# breaking_bitcoin.net
KiCad netlist of a schematic drawn in EAGLE
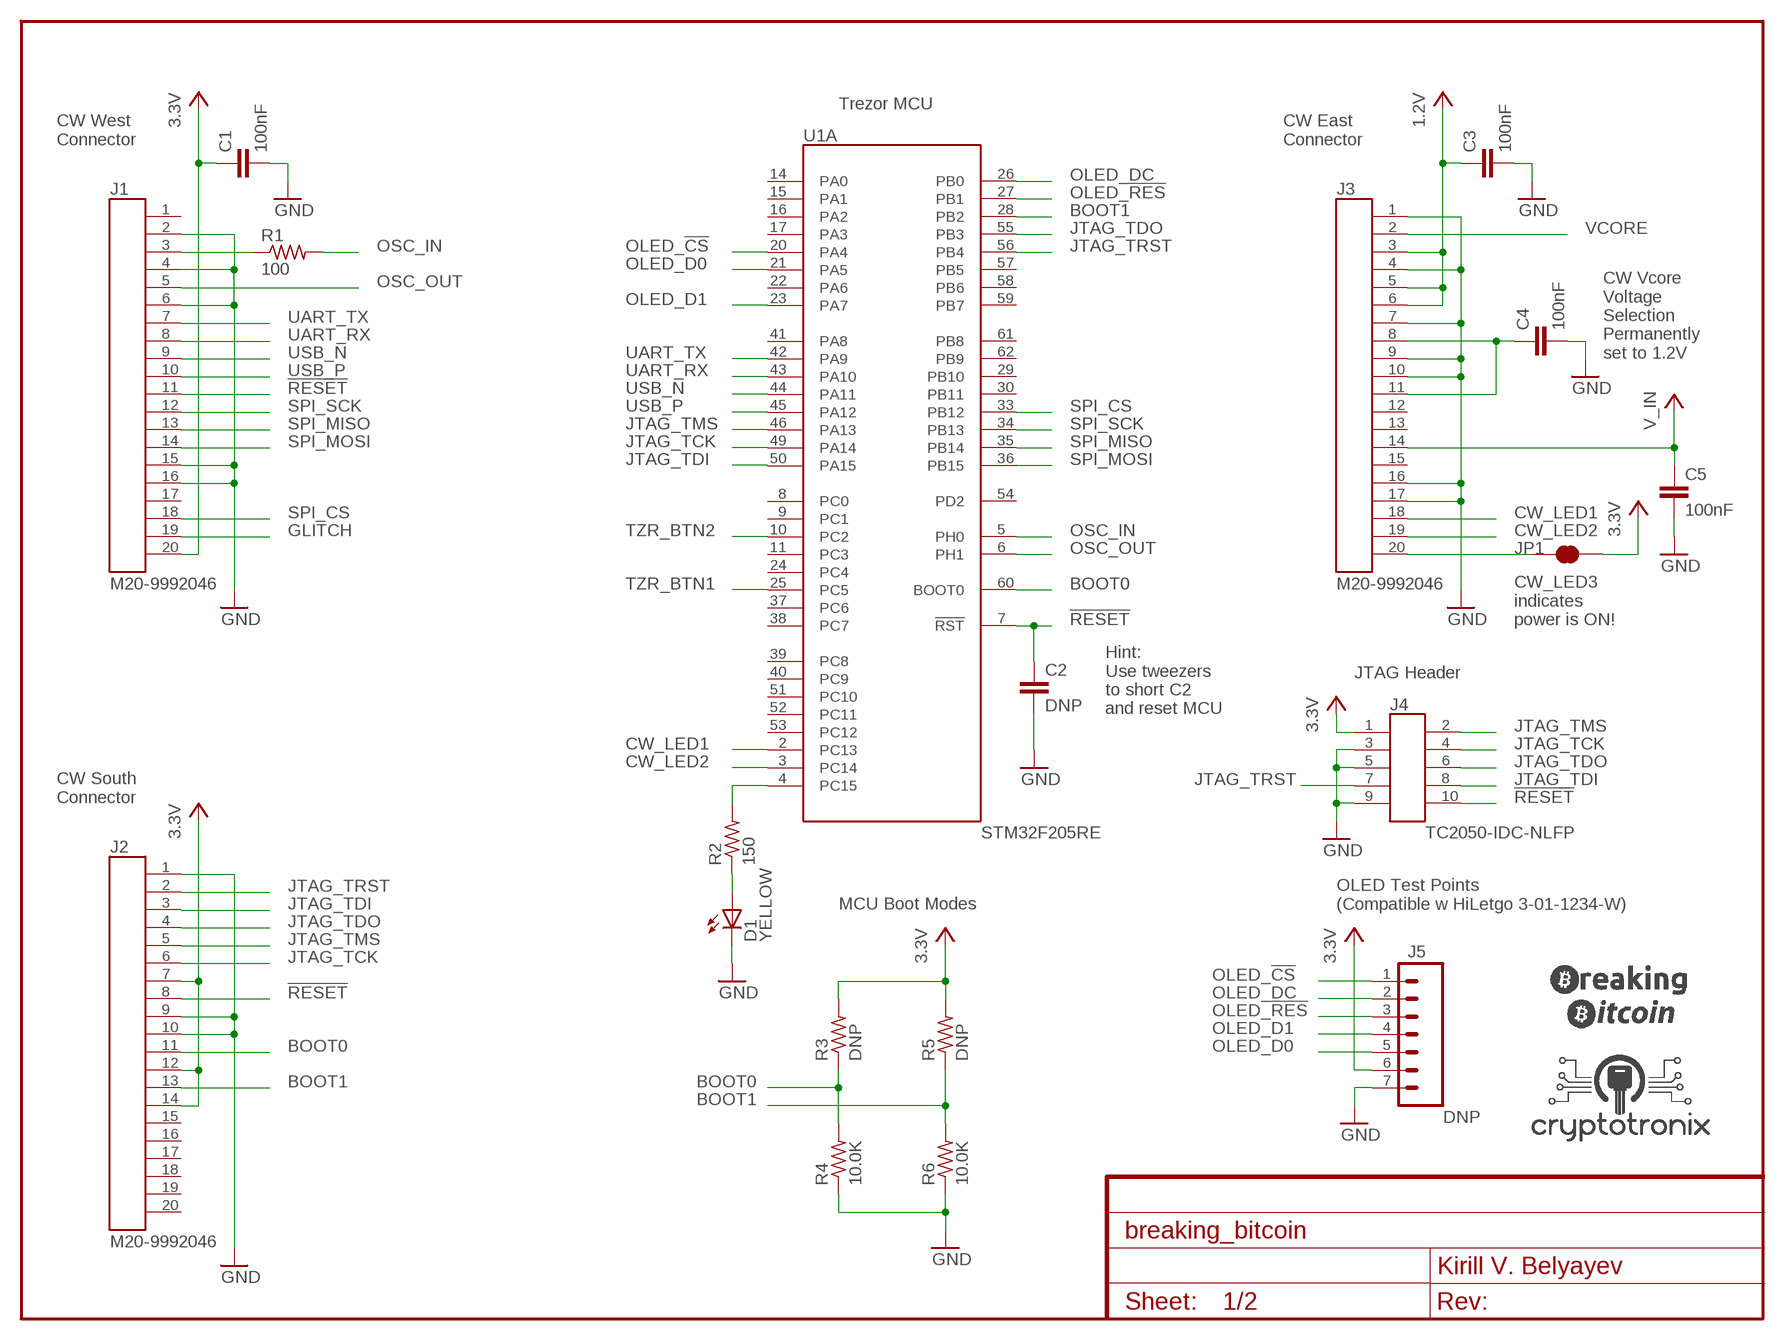
[diagram p0: schematic, sheet 1]
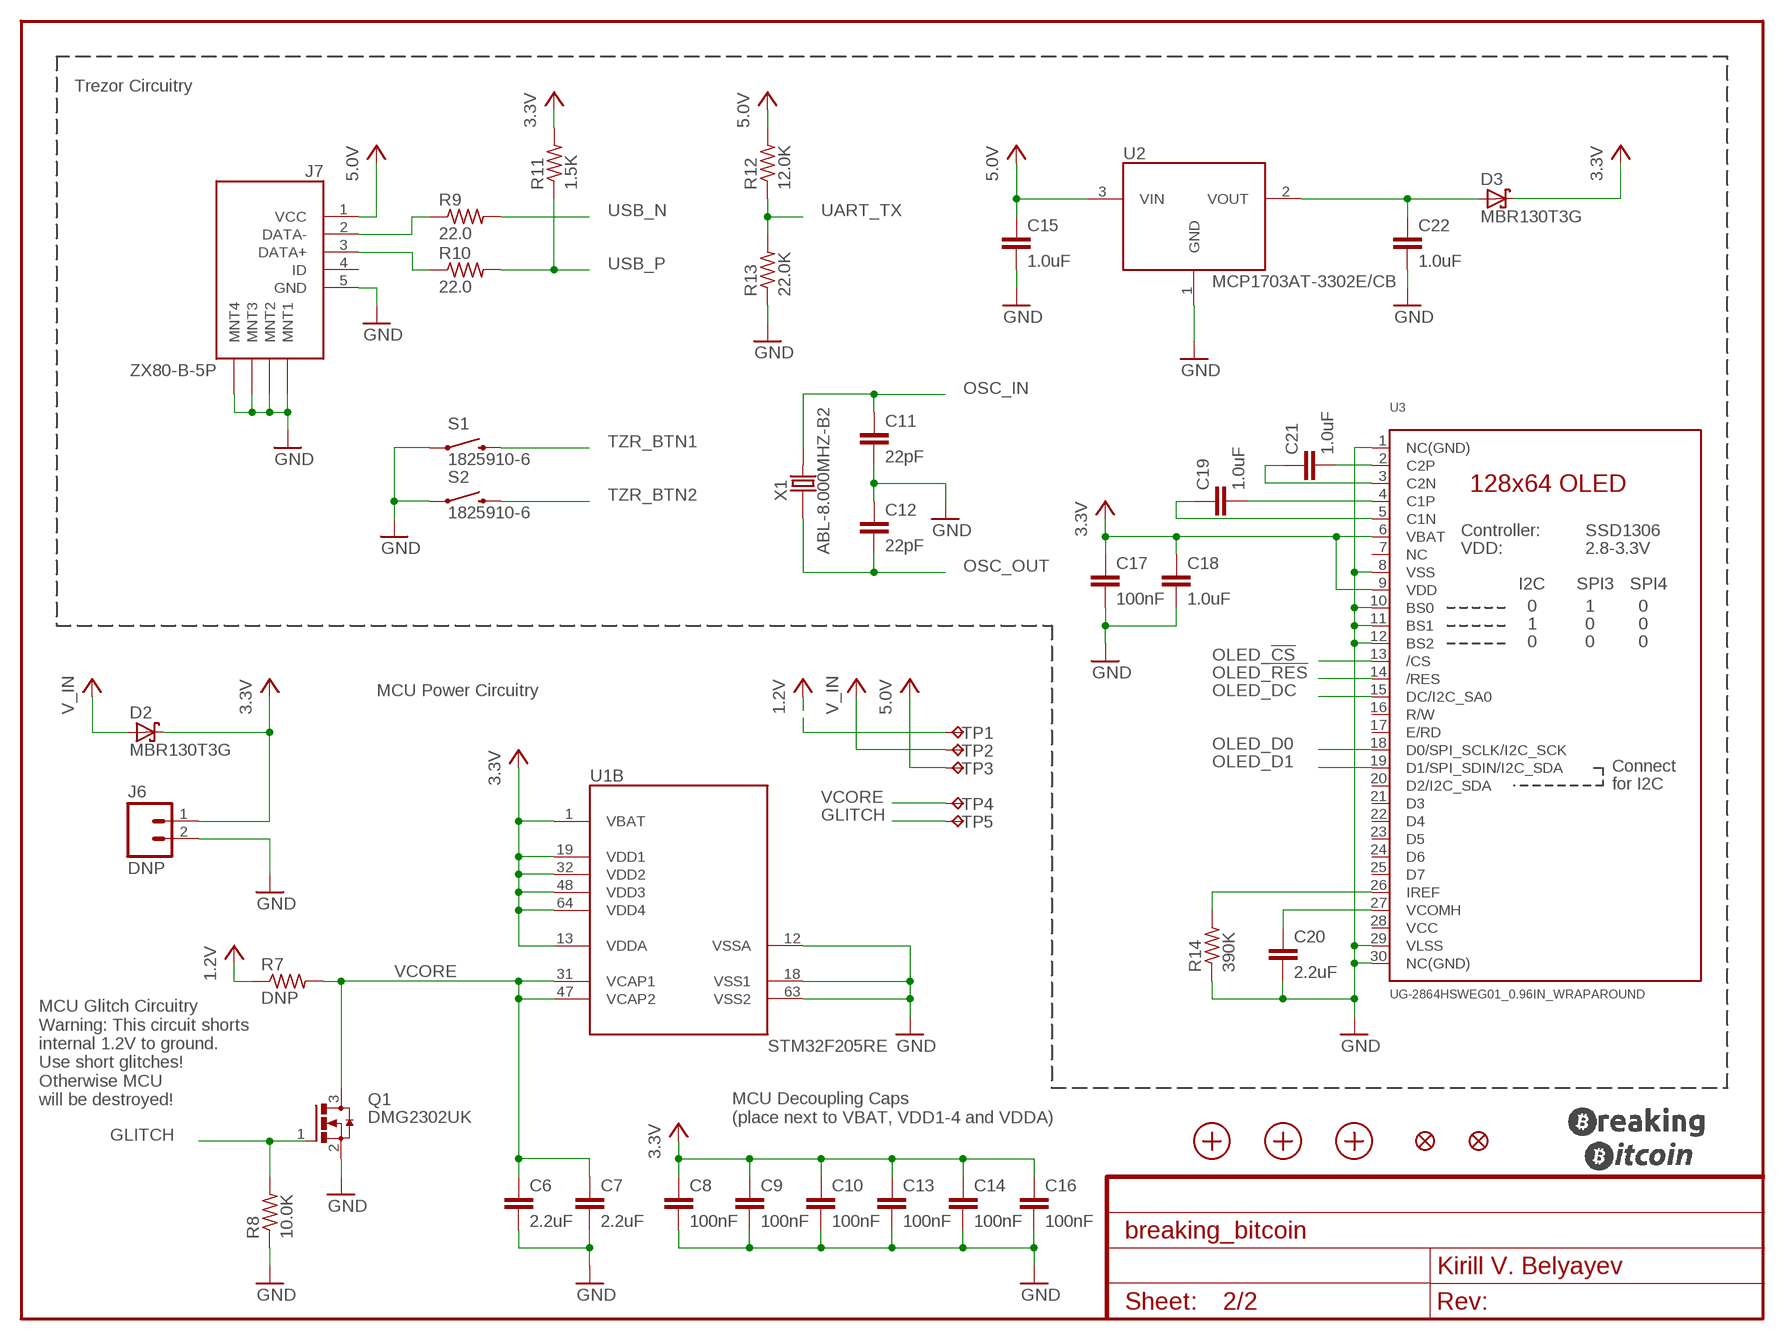
[diagram p1: schematic, sheet 2]

(export (version "E")
  (design (tool "Eeschema 10.0.6"))
  (components
    (comp (ref "C6")
      (value "2.2uF")
      (footprint "eagle-import:C0603")
      (libsource (lib "eagle-import") (part "C-EUC0603"))
    )
    (comp (ref "C7")
      (value "2.2uF")
      (footprint "eagle-import:C0603")
      (libsource (lib "eagle-import") (part "C-EUC0603"))
    )
    (comp (ref "C8")
      (value "100nF")
      (footprint "eagle-import:C0603")
      (libsource (lib "eagle-import") (part "C-EUC0603"))
    )
    (comp (ref "C9")
      (value "100nF")
      (footprint "eagle-import:C0603")
      (libsource (lib "eagle-import") (part "C-EUC0603"))
    )
    (comp (ref "C10")
      (value "100nF")
      (footprint "eagle-import:C0603")
      (libsource (lib "eagle-import") (part "C-EUC0603"))
    )
    (comp (ref "C11")
      (value "22pF")
      (footprint "eagle-import:C0603")
      (libsource (lib "eagle-import") (part "C-EUC0603"))
    )
    (comp (ref "C12")
      (value "22pF")
      (footprint "eagle-import:C0603")
      (libsource (lib "eagle-import") (part "C-EUC0603"))
    )
    (comp (ref "C13")
      (value "100nF")
      (footprint "eagle-import:C0603")
      (libsource (lib "eagle-import") (part "C-EUC0603"))
    )
    (comp (ref "C14")
      (value "100nF")
      (footprint "eagle-import:C0603")
      (libsource (lib "eagle-import") (part "C-EUC0603"))
    )
    (comp (ref "C15")
      (value "1.0uF")
      (footprint "eagle-import:C0603")
      (libsource (lib "eagle-import") (part "C-EUC0603"))
    )
    (comp (ref "C16")
      (value "100nF")
      (footprint "eagle-import:C0603")
      (libsource (lib "eagle-import") (part "C-EUC0603"))
    )
    (comp (ref "C17")
      (value "100nF")
      (footprint "eagle-import:C0603")
      (libsource (lib "eagle-import") (part "C-EUC0603"))
    )
    (comp (ref "C18")
      (value "1.0uF")
      (footprint "eagle-import:C0603")
      (libsource (lib "eagle-import") (part "C-EUC0603"))
    )
    (comp (ref "C19")
      (value "1.0uF")
      (footprint "eagle-import:C0603")
      (libsource (lib "eagle-import") (part "C-EUC0603"))
    )
    (comp (ref "C20")
      (value "2.2uF")
      (footprint "eagle-import:C0603")
      (libsource (lib "eagle-import") (part "C-EUC0603"))
    )
    (comp (ref "C21")
      (value "1.0uF")
      (footprint "eagle-import:C0603")
      (libsource (lib "eagle-import") (part "C-EUC0603"))
    )
    (comp (ref "C22")
      (value "1.0uF")
      (footprint "eagle-import:C0603")
      (libsource (lib "eagle-import") (part "C-EUC0603"))
    )
    (comp (ref "D2")
      (value "MBR130T3G")
      (footprint "eagle-import:SOD123")
      (fields (field (name "MANUFACTURER") "ON Semiconductor"))
      (libsource (lib "eagle-import") (part "MBR130T3G"))
    )
    (comp (ref "D3")
      (value "MBR130T3G")
      (footprint "eagle-import:SOD123")
      (fields (field (name "MANUFACTURER") "ON Semiconductor"))
      (libsource (lib "eagle-import") (part "MBR130T3G"))
    )
    (comp (ref "FD1")
      (value "FIDUCIALUFIDUCIAL")
      (footprint "eagle-import:MICRO-FIDUCIAL")
      (libsource (lib "eagle-import") (part "FIDUCIALUFIDUCIAL"))
    )
    (comp (ref "FD2")
      (value "FIDUCIALUFIDUCIAL")
      (footprint "eagle-import:MICRO-FIDUCIAL")
      (libsource (lib "eagle-import") (part "FIDUCIALUFIDUCIAL"))
    )
    (comp (ref "J6")
      (value "DNP")
      (footprint "eagle-import:M20-9990246")
      (fields (field (name "MAN-PART_NUM") "M20-9990246") (field (name "MANUFACTURER") "Harwin Inc."))
      (libsource (lib "eagle-import") (part "M20-9990246"))
    )
    (comp (ref "J7")
      (value "ZX80-B-5P")
      (footprint "eagle-import:ZX80-B-5P")
      (fields (field (name "MAN-PART_NUM") "ZX80-B-5P(30)") (field (name "MANUFACTURER") "Hirose"))
      (libsource (lib "eagle-import") (part "ZX80-B-5P"))
    )
    (comp (ref "MNT1")
      (value "MOUNT-HOLE-NO-PLATE4-40")
      (footprint "eagle-import:MOUNT-HOLE-NO-PLATE-4-40")
      (libsource (lib "eagle-import") (part "MOUNT-HOLE-NO-PLATE4-40"))
    )
    (comp (ref "MNT2")
      (value "MOUNT-HOLE-NO-PLATE4-40")
      (footprint "eagle-import:MOUNT-HOLE-NO-PLATE-4-40")
      (libsource (lib "eagle-import") (part "MOUNT-HOLE-NO-PLATE4-40"))
    )
    (comp (ref "MNT3")
      (value "MOUNT-HOLE-NO-PLATE4-40")
      (footprint "eagle-import:MOUNT-HOLE-NO-PLATE-4-40")
      (libsource (lib "eagle-import") (part "MOUNT-HOLE-NO-PLATE4-40"))
    )
    (comp (ref "Q1")
      (value "DMG2302UK")
      (footprint "eagle-import:DMG2302UK")
      (fields (field (name "MANUFACTURER") "Diodes Inc."))
      (libsource (lib "eagle-import") (part "DMG2302UK"))
    )
    (comp (ref "R7")
      (value "DNP")
      (footprint "eagle-import:R0603")
      (libsource (lib "eagle-import") (part "R-US_R0603"))
    )
    (comp (ref "R8")
      (value "10.0K")
      (footprint "eagle-import:R0603")
      (libsource (lib "eagle-import") (part "R-US_R0603"))
    )
    (comp (ref "R9")
      (value "22.0")
      (footprint "eagle-import:R0603")
      (libsource (lib "eagle-import") (part "R-US_R0603"))
    )
    (comp (ref "R10")
      (value "22.0")
      (footprint "eagle-import:R0603")
      (libsource (lib "eagle-import") (part "R-US_R0603"))
    )
    (comp (ref "R11")
      (value "1.5K")
      (footprint "eagle-import:R0603")
      (libsource (lib "eagle-import") (part "R-US_R0603"))
    )
    (comp (ref "R12")
      (value "12.0K")
      (footprint "eagle-import:R0603")
      (libsource (lib "eagle-import") (part "R-US_R0603"))
    )
    (comp (ref "R13")
      (value "22.0K")
      (footprint "eagle-import:R0603")
      (libsource (lib "eagle-import") (part "R-US_R0603"))
    )
    (comp (ref "R14")
      (value "390K")
      (footprint "eagle-import:R0603")
      (libsource (lib "eagle-import") (part "R-US_R0603"))
    )
    (comp (ref "S1")
      (value "1825910-6")
      (footprint "eagle-import:SWITCH-TACT-TH")
      (fields
        (field (name "MANUFACTURER") "TE Connectivity")
        (field (name "MAN-PART_NUM") "1825910-6")
        (field (name "MANUFACTURER_1") "TE Connectivity")
      )
      (libsource (lib "eagle-import") (part "SWITCH-TACT-TH"))
    )
    (comp (ref "S2")
      (value "1825910-6")
      (footprint "eagle-import:SWITCH-TACT-TH")
      (fields
        (field (name "MANUFACTURER") "TE Connectivity")
        (field (name "MAN-PART_NUM") "1825910-6")
        (field (name "MANUFACTURER_1") "TE Connectivity")
      )
      (libsource (lib "eagle-import") (part "SWITCH-TACT-TH"))
    )
    (comp (ref "TP1")
      (value "TEST-POINT40MIL")
      (footprint "eagle-import:TEST-POINT-40MILL")
      (libsource (lib "eagle-import") (part "TEST-POINT40MIL"))
    )
    (comp (ref "TP2")
      (value "TEST-POINT40MIL")
      (footprint "eagle-import:TEST-POINT-40MILL")
      (libsource (lib "eagle-import") (part "TEST-POINT40MIL"))
    )
    (comp (ref "TP3")
      (value "TEST-POINT40MIL")
      (footprint "eagle-import:TEST-POINT-40MILL")
      (libsource (lib "eagle-import") (part "TEST-POINT40MIL"))
    )
    (comp (ref "TP4")
      (value "TEST-POINT40MIL")
      (footprint "eagle-import:TEST-POINT-40MILL")
      (libsource (lib "eagle-import") (part "TEST-POINT40MIL"))
    )
    (comp (ref "TP5")
      (value "TEST-POINT40MIL")
      (footprint "eagle-import:TEST-POINT-40MILL")
      (libsource (lib "eagle-import") (part "TEST-POINT40MIL"))
    )
    (comp (ref "U$3")
      (value "BB_LOGO")
      (footprint "eagle-import:BB_LOGO")
      (libsource (lib "eagle-import") (part "BB_LOGO"))
    )
    (comp (ref "U1")
      (value "STM32F205RE")
      (footprint "eagle-import:LQFP64")
      (fields (field (name "MANUFACTURER") "STMicroelectronics"))
      (libsource (lib "eagle-import") (part "STM32F205RE"))
    )
    (comp (ref "U2")
      (value "MCP1703AT-3302E/CB")
      (footprint "eagle-import:MCP1703AT-3302E_CB")
      (fields (field (name "MANUFACTURER") "Microchip Technology"))
      (libsource (lib "eagle-import") (part "MCP1703AT-3302E/CB"))
    )
    (comp (ref "U3")
      (value "UG-2864HSWEG01_0.96IN_WRAPAROUND")
      (footprint "eagle-import:UG-2864HSWEG01_0.96IN_WRAPAROUND")
      (libsource (lib "eagle-import") (part "DISP_OLED_UG-2864HSWEG010.96{dblquote}"))
    )
    (comp (ref "X1")
      (value "ABL-8.000MHZ-B2")
      (footprint "eagle-import:ABL-8.000MHZ-B2")
      (fields (field (name "MANUFACTURER") "Abracon"))
      (libsource (lib "eagle-import") (part "ABL-8.000MHZ-B2"))
    )
    (comp (ref "C1")
      (value "100nF")
      (footprint "eagle-import:C0603")
      (libsource (lib "eagle-import") (part "C-EUC0603"))
    )
    (comp (ref "C2")
      (value "DNP")
      (footprint "eagle-import:C0603")
      (libsource (lib "eagle-import") (part "C-EUC0603"))
    )
    (comp (ref "C3")
      (value "100nF")
      (footprint "eagle-import:C0603")
      (libsource (lib "eagle-import") (part "C-EUC0603"))
    )
    (comp (ref "C4")
      (value "100nF")
      (footprint "eagle-import:C0603")
      (libsource (lib "eagle-import") (part "C-EUC0603"))
    )
    (comp (ref "C5")
      (value "100nF")
      (footprint "eagle-import:C0603")
      (libsource (lib "eagle-import") (part "C-EUC0603"))
    )
    (comp (ref "D1")
      (value "YELLOW")
      (footprint "eagle-import:0603")
      (fields (field (name "MAN-PART_NUM") "LTST-C190") (field (name "MANUFACTURER") "Lite-On Inc."))
      (libsource (lib "eagle-import") (part "LTST-C190YKT"))
    )
    (comp (ref "J1")
      (value "M20-9992046")
      (footprint "eagle-import:M20-9992046")
      (fields (field (name "MANUFACTURER") "Harwin Inc."))
      (libsource (lib "eagle-import") (part "M20-9992046"))
    )
    (comp (ref "J2")
      (value "M20-9992046")
      (footprint "eagle-import:M20-9992046")
      (fields (field (name "MANUFACTURER") "Harwin Inc."))
      (libsource (lib "eagle-import") (part "M20-9992046"))
    )
    (comp (ref "J3")
      (value "M20-9992046")
      (footprint "eagle-import:M20-9992046")
      (fields (field (name "MANUFACTURER") "Harwin Inc."))
      (libsource (lib "eagle-import") (part "M20-9992046"))
    )
    (comp (ref "J4")
      (value "TC2050-IDC-NLFP")
      (footprint "eagle-import:TC2050-IDC-NLFP")
      (fields (field (name "MANUFACTURER") "Tag Connect"))
      (libsource (lib "eagle-import") (part "TC2050-IDC-NLFP"))
    )
    (comp (ref "J5")
      (value "DNP")
      (footprint "eagle-import:1X07")
      (libsource (lib "eagle-import") (part "M07"))
    )
    (comp (ref "JP1")
      (value "JUMPER-PAD-2-NC_BY_TRACE")
      (footprint "eagle-import:PAD-JUMPER-2-NC_BY_TRACE_YES_SILK")
      (libsource (lib "eagle-import") (part "JUMPER-PAD-2-NC_BY_TRACE"))
    )
    (comp (ref "R1")
      (value "100")
      (footprint "eagle-import:R0603")
      (libsource (lib "eagle-import") (part "R-US_R0603"))
    )
    (comp (ref "R2")
      (value "150")
      (footprint "eagle-import:R0603")
      (libsource (lib "eagle-import") (part "R-US_R0603"))
    )
    (comp (ref "R3")
      (value "DNP")
      (footprint "eagle-import:R0603")
      (libsource (lib "eagle-import") (part "R-US_R0603"))
    )
    (comp (ref "R4")
      (value "10.0K")
      (footprint "eagle-import:R0603")
      (libsource (lib "eagle-import") (part "R-US_R0603"))
    )
    (comp (ref "R5")
      (value "DNP")
      (footprint "eagle-import:R0603")
      (libsource (lib "eagle-import") (part "R-US_R0603"))
    )
    (comp (ref "R6")
      (value "10.0K")
      (footprint "eagle-import:R0603")
      (libsource (lib "eagle-import") (part "R-US_R0603"))
    )
    (comp (ref "U$1")
      (value "BB_LOGO")
      (footprint "eagle-import:BB_LOGO")
      (libsource (lib "eagle-import") (part "BB_LOGO"))
    )
    (comp (ref "U$2")
      (value "CRYPTOTRONIX_LOGO")
      (footprint "eagle-import:CRYPTOTRONIX_LOGO")
      (libsource (lib "eagle-import") (part "CRYPTOTRONIX_LOGO"))
    )
  )
  (nets
    (net (code "1") (name "0V") (class "Default")
      (node (ref "C1") (pin "2") (pinfunction "2_2") (pintype "passive"))
      (node (ref "C10") (pin "2") (pinfunction "2_2") (pintype "passive"))
      (node (ref "C11") (pin "2") (pinfunction "2_2") (pintype "passive"))
      (node (ref "C12") (pin "1") (pinfunction "1_1") (pintype "passive"))
      (node (ref "C13") (pin "2") (pinfunction "2_2") (pintype "passive"))
      (node (ref "C14") (pin "2") (pinfunction "2_2") (pintype "passive"))
      (node (ref "C15") (pin "2") (pinfunction "2_2") (pintype "passive"))
      (node (ref "C16") (pin "2") (pinfunction "2_2") (pintype "passive"))
      (node (ref "C17") (pin "2") (pinfunction "2_2") (pintype "passive"))
      (node (ref "C18") (pin "2") (pinfunction "2_2") (pintype "passive"))
      (node (ref "C2") (pin "2") (pinfunction "2_2") (pintype "passive"))
      (node (ref "C20") (pin "2") (pinfunction "2_2") (pintype "passive"))
      (node (ref "C22") (pin "2") (pinfunction "2_2") (pintype "passive"))
      (node (ref "C3") (pin "2") (pinfunction "2_2") (pintype "passive"))
      (node (ref "C4") (pin "2") (pinfunction "2_2") (pintype "passive"))
      (node (ref "C5") (pin "2") (pinfunction "2_2") (pintype "passive"))
      (node (ref "C6") (pin "2") (pinfunction "2_2") (pintype "passive"))
      (node (ref "C7") (pin "2") (pinfunction "2_2") (pintype "passive"))
      (node (ref "C8") (pin "2") (pinfunction "2_2") (pintype "passive"))
      (node (ref "C9") (pin "2") (pinfunction "2_2") (pintype "passive"))
      (node (ref "D1") (pin "C") (pinfunction "C_C") (pintype "passive"))
      (node (ref "J1") (pin "15") (pinfunction "P$15_15") (pintype "bidirectional"))
      (node (ref "J1") (pin "16") (pinfunction "P$16_16") (pintype "bidirectional"))
      (node (ref "J1") (pin "2") (pinfunction "P$2_2") (pintype "bidirectional"))
      (node (ref "J1") (pin "4") (pinfunction "P$4_4") (pintype "bidirectional"))
      (node (ref "J1") (pin "6") (pinfunction "P$6_6") (pintype "bidirectional"))
      (node (ref "J2") (pin "1") (pinfunction "P$1_1") (pintype "bidirectional"))
      (node (ref "J2") (pin "10") (pinfunction "P$10_10") (pintype "bidirectional"))
      (node (ref "J2") (pin "9") (pinfunction "P$9_9") (pintype "bidirectional"))
      (node (ref "J3") (pin "1") (pinfunction "P$1_1") (pintype "bidirectional"))
      (node (ref "J3") (pin "10") (pinfunction "P$10_10") (pintype "bidirectional"))
      (node (ref "J3") (pin "16") (pinfunction "P$16_16") (pintype "bidirectional"))
      (node (ref "J3") (pin "17") (pinfunction "P$17_17") (pintype "bidirectional"))
      (node (ref "J3") (pin "4") (pinfunction "P$4_4") (pintype "bidirectional"))
      (node (ref "J3") (pin "7") (pinfunction "P$7_7") (pintype "bidirectional"))
      (node (ref "J3") (pin "9") (pinfunction "P$9_9") (pintype "bidirectional"))
      (node (ref "J4") (pin "3") (pinfunction "P$3_3") (pintype "bidirectional"))
      (node (ref "J4") (pin "5") (pinfunction "P$5_5") (pintype "bidirectional"))
      (node (ref "J4") (pin "9") (pinfunction "P$9_9") (pintype "bidirectional"))
      (node (ref "J5") (pin "7") (pinfunction "7_7") (pintype "passive"))
      (node (ref "J6") (pin "2") (pinfunction "2_2") (pintype "passive"))
      (node (ref "J7") (pin "5") (pinfunction "GND_5") (pintype "bidirectional"))
      (node (ref "J7") (pin "M1") (pinfunction "MNT1_M1") (pintype "bidirectional"))
      (node (ref "J7") (pin "M2") (pinfunction "MNT2_M2") (pintype "bidirectional"))
      (node (ref "J7") (pin "M3") (pinfunction "MNT3_M3") (pintype "bidirectional"))
      (node (ref "J7") (pin "M4") (pinfunction "MNT4_M4") (pintype "bidirectional"))
      (node (ref "Q1") (pin "2") (pinfunction "S_2") (pintype "passive"))
      (node (ref "R13") (pin "1") (pinfunction "1_1") (pintype "passive"))
      (node (ref "R14") (pin "1") (pinfunction "1_1") (pintype "passive"))
      (node (ref "R4") (pin "1") (pinfunction "1_1") (pintype "passive"))
      (node (ref "R6") (pin "1") (pinfunction "1_1") (pintype "passive"))
      (node (ref "R8") (pin "1") (pinfunction "1_1") (pintype "passive"))
      (node (ref "S1") (pin "1") (pinfunction "1_1") (pintype "passive"))
      (node (ref "S2") (pin "1") (pinfunction "1_1") (pintype "passive"))
      (node (ref "U1") (pin "12") (pinfunction "VSSA_12") (pintype "bidirectional"))
      (node (ref "U1") (pin "18") (pinfunction "VSS1_18") (pintype "bidirectional"))
      (node (ref "U1") (pin "63") (pinfunction "VSS2_63") (pintype "bidirectional"))
      (node (ref "U2") (pin "1") (pinfunction "GND_1") (pintype "bidirectional"))
      (node (ref "U3") (pin "1") (pinfunction "NC(GND)_1") (pintype "input"))
      (node (ref "U3") (pin "10") (pinfunction "BS0_10") (pintype "input"))
      (node (ref "U3") (pin "11") (pinfunction "BS1_11") (pintype "input"))
      (node (ref "U3") (pin "12") (pinfunction "BS2_12") (pintype "input"))
      (node (ref "U3") (pin "29") (pinfunction "VLSS_29") (pintype "power_in"))
      (node (ref "U3") (pin "30") (pinfunction "NC(GND)_30") (pintype "input"))
      (node (ref "U3") (pin "8") (pinfunction "VSS_8") (pintype "power_in"))
    )
    (net (code "2") (name "1.2V") (class "Default")
      (node (ref "C3") (pin "1") (pinfunction "1_1") (pintype "passive"))
      (node (ref "J3") (pin "3") (pinfunction "P$3_3") (pintype "bidirectional"))
      (node (ref "J3") (pin "5") (pinfunction "P$5_5") (pintype "bidirectional"))
      (node (ref "J3") (pin "6") (pinfunction "P$6_6") (pintype "bidirectional"))
      (node (ref "R7") (pin "1") (pinfunction "1_1") (pintype "passive"))
      (node (ref "TP1") (pin "1") (pinfunction "PP_1") (pintype "input"))
    )
    (net (code "3") (name "3.3V") (class "Default")
      (node (ref "C1") (pin "1") (pinfunction "1_1") (pintype "passive"))
      (node (ref "C10") (pin "1") (pinfunction "1_1") (pintype "passive"))
      (node (ref "C13") (pin "1") (pinfunction "1_1") (pintype "passive"))
      (node (ref "C14") (pin "1") (pinfunction "1_1") (pintype "passive"))
      (node (ref "C16") (pin "1") (pinfunction "1_1") (pintype "passive"))
      (node (ref "C17") (pin "1") (pinfunction "1_1") (pintype "passive"))
      (node (ref "C18") (pin "1") (pinfunction "1_1") (pintype "passive"))
      (node (ref "C8") (pin "1") (pinfunction "1_1") (pintype "passive"))
      (node (ref "C9") (pin "1") (pinfunction "1_1") (pintype "passive"))
      (node (ref "D2") (pin "C") (pinfunction "C_C") (pintype "passive"))
      (node (ref "D3") (pin "C") (pinfunction "C_C") (pintype "passive"))
      (node (ref "J1") (pin "20") (pinfunction "P$20_20") (pintype "bidirectional"))
      (node (ref "J2") (pin "12") (pinfunction "P$12_12") (pintype "bidirectional"))
      (node (ref "J2") (pin "14") (pinfunction "P$14_14") (pintype "bidirectional"))
      (node (ref "J2") (pin "7") (pinfunction "P$7_7") (pintype "bidirectional"))
      (node (ref "J4") (pin "1") (pinfunction "P$1_1") (pintype "bidirectional"))
      (node (ref "J5") (pin "6") (pinfunction "6_6") (pintype "passive"))
      (node (ref "J6") (pin "1") (pinfunction "1_1") (pintype "passive"))
      (node (ref "JP1") (pin "2") (pinfunction "2_2") (pintype "passive"))
      (node (ref "R11") (pin "2") (pinfunction "2_2") (pintype "passive"))
      (node (ref "R3") (pin "2") (pinfunction "2_2") (pintype "passive"))
      (node (ref "R5") (pin "2") (pinfunction "2_2") (pintype "passive"))
      (node (ref "U1") (pin "1") (pinfunction "VBAT_1") (pintype "bidirectional"))
      (node (ref "U1") (pin "13") (pinfunction "VDDA_13") (pintype "bidirectional"))
      (node (ref "U1") (pin "19") (pinfunction "VDD1_19") (pintype "bidirectional"))
      (node (ref "U1") (pin "32") (pinfunction "VDD2_32") (pintype "bidirectional"))
      (node (ref "U1") (pin "48") (pinfunction "VDD3_48") (pintype "bidirectional"))
      (node (ref "U1") (pin "64") (pinfunction "VDD4_64") (pintype "bidirectional"))
      (node (ref "U3") (pin "6") (pinfunction "VBAT_6") (pintype "input"))
      (node (ref "U3") (pin "9") (pinfunction "VDD_9") (pintype "power_in"))
    )
    (net (code "4") (name "5.0V") (class "Default")
      (node (ref "C15") (pin "1") (pinfunction "1_1") (pintype "passive"))
      (node (ref "J7") (pin "1") (pinfunction "VCC_1") (pintype "bidirectional"))
      (node (ref "R12") (pin "2") (pinfunction "2_2") (pintype "passive"))
      (node (ref "TP3") (pin "1") (pinfunction "PP_1") (pintype "input"))
      (node (ref "U2") (pin "3") (pinfunction "VIN_3") (pintype "bidirectional"))
    )
    (net (code "5") (name "BOOT0") (class "Default")
      (node (ref "J2") (pin "11") (pinfunction "P$11_11") (pintype "bidirectional"))
      (node (ref "R3") (pin "1") (pinfunction "1_1") (pintype "passive"))
      (node (ref "R4") (pin "2") (pinfunction "2_2") (pintype "passive"))
      (node (ref "U1") (pin "60") (pinfunction "BOOT0_60") (pintype "bidirectional"))
    )
    (net (code "6") (name "BOOT1") (class "Default")
      (node (ref "J2") (pin "13") (pinfunction "P$13_13") (pintype "bidirectional"))
      (node (ref "R5") (pin "1") (pinfunction "1_1") (pintype "passive"))
      (node (ref "R6") (pin "2") (pinfunction "2_2") (pintype "passive"))
      (node (ref "U1") (pin "28") (pinfunction "PB2_28") (pintype "bidirectional"))
    )
    (net (code "7") (name "CW_LED1") (class "Default")
      (node (ref "J3") (pin "18") (pinfunction "P$18_18") (pintype "bidirectional"))
      (node (ref "U1") (pin "2") (pinfunction "PC13_2") (pintype "bidirectional"))
    )
    (net (code "8") (name "CW_LED2") (class "Default")
      (node (ref "J3") (pin "19") (pinfunction "P$19_19") (pintype "bidirectional"))
      (node (ref "U1") (pin "3") (pinfunction "PC14_3") (pintype "bidirectional"))
    )
    (net (code "9") (name "GLITCH") (class "Default")
      (node (ref "J1") (pin "19") (pinfunction "P$19_19") (pintype "bidirectional"))
      (node (ref "Q1") (pin "1") (pinfunction "G_1") (pintype "passive"))
      (node (ref "R8") (pin "2") (pinfunction "2_2") (pintype "passive"))
      (node (ref "TP5") (pin "1") (pinfunction "PP_1") (pintype "input"))
    )
    (net (code "10") (name "JTAG_TCK") (class "Default")
      (node (ref "J2") (pin "6") (pinfunction "P$6_6") (pintype "bidirectional"))
      (node (ref "J4") (pin "4") (pinfunction "P$4_4") (pintype "bidirectional"))
      (node (ref "U1") (pin "49") (pinfunction "PA14_49") (pintype "bidirectional"))
    )
    (net (code "11") (name "JTAG_TDI") (class "Default")
      (node (ref "J2") (pin "3") (pinfunction "P$3_3") (pintype "bidirectional"))
      (node (ref "J4") (pin "8") (pinfunction "P$8_8") (pintype "bidirectional"))
      (node (ref "U1") (pin "50") (pinfunction "PA15_50") (pintype "bidirectional"))
    )
    (net (code "12") (name "JTAG_TDO") (class "Default")
      (node (ref "J2") (pin "4") (pinfunction "P$4_4") (pintype "bidirectional"))
      (node (ref "J4") (pin "6") (pinfunction "P$6_6") (pintype "bidirectional"))
      (node (ref "U1") (pin "55") (pinfunction "PB3_55") (pintype "bidirectional"))
    )
    (net (code "13") (name "JTAG_TMS") (class "Default")
      (node (ref "J2") (pin "5") (pinfunction "P$5_5") (pintype "bidirectional"))
      (node (ref "J4") (pin "2") (pinfunction "P$2_2") (pintype "bidirectional"))
      (node (ref "U1") (pin "46") (pinfunction "PA13_46") (pintype "bidirectional"))
    )
    (net (code "14") (name "JTAG_TRST") (class "Default")
      (node (ref "J2") (pin "2") (pinfunction "P$2_2") (pintype "bidirectional"))
      (node (ref "J4") (pin "7") (pinfunction "P$7_7") (pintype "bidirectional"))
      (node (ref "U1") (pin "56") (pinfunction "PB4_56") (pintype "bidirectional"))
    )
    (net (code "15") (name "Net-(D1-PadA)") (class "Default")
      (node (ref "D1") (pin "A") (pinfunction "A_A") (pintype "passive"))
      (node (ref "R2") (pin "1") (pinfunction "1_1") (pintype "passive"))
    )
    (net (code "16") (name "Net-(J1-P$3)") (class "Default")
      (node (ref "J1") (pin "3") (pinfunction "P$3_3") (pintype "bidirectional"))
      (node (ref "R1") (pin "1") (pinfunction "1_1") (pintype "passive"))
    )
    (net (code "17") (name "Net-(J3-P$11)") (class "Default")
      (node (ref "C4") (pin "1") (pinfunction "1_1") (pintype "passive"))
      (node (ref "J3") (pin "11") (pinfunction "P$11_11") (pintype "bidirectional"))
      (node (ref "J3") (pin "8") (pinfunction "P$8_8") (pintype "bidirectional"))
    )
    (net (code "18") (name "Net-(J3-P$20)") (class "Default")
      (node (ref "J3") (pin "20") (pinfunction "P$20_20") (pintype "bidirectional"))
      (node (ref "JP1") (pin "1") (pinfunction "1_1") (pintype "passive"))
    )
    (net (code "19") (name "Net-(J7-DATA+)") (class "Default")
      (node (ref "J7") (pin "3") (pinfunction "DATA+_3") (pintype "bidirectional"))
      (node (ref "R10") (pin "1") (pinfunction "1_1") (pintype "passive"))
    )
    (net (code "20") (name "Net-(J7-DATA-)") (class "Default")
      (node (ref "J7") (pin "2") (pinfunction "DATA-_2") (pintype "bidirectional"))
      (node (ref "R9") (pin "1") (pinfunction "1_1") (pintype "passive"))
    )
    (net (code "21") (name "Net-(U1A-PC15)") (class "Default")
      (node (ref "R2") (pin "2") (pinfunction "2_2") (pintype "passive"))
      (node (ref "U1") (pin "4") (pinfunction "PC15_4") (pintype "bidirectional"))
    )
    (net (code "22") (name "Net-(U2-VOUT)") (class "Default")
      (node (ref "C22") (pin "1") (pinfunction "1_1") (pintype "passive"))
      (node (ref "D3") (pin "A") (pinfunction "A_A") (pintype "passive"))
      (node (ref "U2") (pin "2") (pinfunction "VOUT_2") (pintype "bidirectional"))
    )
    (net (code "23") (name "Net-(U3-C1N)") (class "Default")
      (node (ref "C19") (pin "1") (pinfunction "1_1") (pintype "passive"))
      (node (ref "U3") (pin "5") (pinfunction "C1N_5") (pintype "input"))
    )
    (net (code "24") (name "Net-(U3-C1P)") (class "Default")
      (node (ref "C19") (pin "2") (pinfunction "2_2") (pintype "passive"))
      (node (ref "U3") (pin "4") (pinfunction "C1P_4") (pintype "input"))
    )
    (net (code "25") (name "Net-(U3-C2N)") (class "Default")
      (node (ref "C21") (pin "1") (pinfunction "1_1") (pintype "passive"))
      (node (ref "U3") (pin "3") (pinfunction "C2N_3") (pintype "input"))
    )
    (net (code "26") (name "Net-(U3-C2P)") (class "Default")
      (node (ref "C21") (pin "2") (pinfunction "2_2") (pintype "passive"))
      (node (ref "U3") (pin "2") (pinfunction "C2P_2") (pintype "input"))
    )
    (net (code "27") (name "Net-(U3-IREF)") (class "Default")
      (node (ref "R14") (pin "2") (pinfunction "2_2") (pintype "passive"))
      (node (ref "U3") (pin "26") (pinfunction "IREF_26") (pintype "input"))
    )
    (net (code "28") (name "Net-(U3-VCOMH)") (class "Default")
      (node (ref "C20") (pin "1") (pinfunction "1_1") (pintype "passive"))
      (node (ref "U3") (pin "27") (pinfunction "VCOMH_27") (pintype "output"))
    )
    (net (code "29") (name "OLED_D0") (class "Default")
      (node (ref "J5") (pin "5") (pinfunction "5_5") (pintype "passive"))
      (node (ref "U1") (pin "21") (pinfunction "PA5_21") (pintype "bidirectional"))
      (node (ref "U3") (pin "18") (pinfunction "D0/SPI_SCLK/I2C_SCK_18") (pintype "bidirectional"))
    )
    (net (code "30") (name "OLED_D1") (class "Default")
      (node (ref "J5") (pin "4") (pinfunction "4_4") (pintype "passive"))
      (node (ref "U1") (pin "23") (pinfunction "PA7_23") (pintype "bidirectional"))
      (node (ref "U3") (pin "19") (pinfunction "D1/SPI_SDIN/I2C_SDA_19") (pintype "bidirectional"))
    )
    (net (code "31") (name "OLED_DC") (class "Default")
      (node (ref "J5") (pin "2") (pinfunction "2_2") (pintype "passive"))
      (node (ref "U1") (pin "26") (pinfunction "PB0_26") (pintype "bidirectional"))
      (node (ref "U3") (pin "15") (pinfunction "DC/I2C_SA0_15") (pintype "input"))
    )
    (net (code "32") (name "OLED_~{CS}") (class "Default")
      (node (ref "J5") (pin "1") (pinfunction "1_1") (pintype "passive"))
      (node (ref "U1") (pin "20") (pinfunction "PA4_20") (pintype "bidirectional"))
      (node (ref "U3") (pin "13") (pinfunction "/CS_13") (pintype "input"))
    )
    (net (code "33") (name "OLED_~{RES}") (class "Default")
      (node (ref "J5") (pin "3") (pinfunction "3_3") (pintype "passive"))
      (node (ref "U1") (pin "27") (pinfunction "PB1_27") (pintype "bidirectional"))
      (node (ref "U3") (pin "14") (pinfunction "/RES_14") (pintype "input"))
    )
    (net (code "34") (name "OSC_IN") (class "Default")
      (node (ref "C11") (pin "1") (pinfunction "1_1") (pintype "passive"))
      (node (ref "R1") (pin "2") (pinfunction "2_2") (pintype "passive"))
      (node (ref "U1") (pin "5") (pinfunction "PH0_5") (pintype "bidirectional"))
      (node (ref "X1") (pin "2") (pinfunction "2_2") (pintype "passive"))
    )
    (net (code "35") (name "OSC_OUT") (class "Default")
      (node (ref "C12") (pin "2") (pinfunction "2_2") (pintype "passive"))
      (node (ref "J1") (pin "5") (pinfunction "P$5_5") (pintype "bidirectional"))
      (node (ref "U1") (pin "6") (pinfunction "PH1_6") (pintype "bidirectional"))
      (node (ref "X1") (pin "1") (pinfunction "1_1") (pintype "passive"))
    )
    (net (code "36") (name "SPI_CS") (class "Default")
      (node (ref "J1") (pin "18") (pinfunction "P$18_18") (pintype "bidirectional"))
      (node (ref "U1") (pin "33") (pinfunction "PB12_33") (pintype "bidirectional"))
    )
    (net (code "37") (name "SPI_MISO") (class "Default")
      (node (ref "J1") (pin "13") (pinfunction "P$13_13") (pintype "bidirectional"))
      (node (ref "U1") (pin "35") (pinfunction "PB14_35") (pintype "bidirectional"))
    )
    (net (code "38") (name "SPI_MOSI") (class "Default")
      (node (ref "J1") (pin "14") (pinfunction "P$14_14") (pintype "bidirectional"))
      (node (ref "U1") (pin "36") (pinfunction "PB15_36") (pintype "bidirectional"))
    )
    (net (code "39") (name "SPI_SCK") (class "Default")
      (node (ref "J1") (pin "12") (pinfunction "P$12_12") (pintype "bidirectional"))
      (node (ref "U1") (pin "34") (pinfunction "PB13_34") (pintype "bidirectional"))
    )
    (net (code "40") (name "TZR_BTN1") (class "Default")
      (node (ref "S1") (pin "3") (pinfunction "2_3") (pintype "passive"))
      (node (ref "U1") (pin "25") (pinfunction "PC5_25") (pintype "bidirectional"))
    )
    (net (code "41") (name "TZR_BTN2") (class "Default")
      (node (ref "S2") (pin "3") (pinfunction "2_3") (pintype "passive"))
      (node (ref "U1") (pin "10") (pinfunction "PC2_10") (pintype "bidirectional"))
    )
    (net (code "42") (name "UART_RX") (class "Default")
      (node (ref "J1") (pin "8") (pinfunction "P$8_8") (pintype "bidirectional"))
      (node (ref "U1") (pin "43") (pinfunction "PA10_43") (pintype "bidirectional"))
    )
    (net (code "43") (name "UART_TX") (class "Default")
      (node (ref "J1") (pin "7") (pinfunction "P$7_7") (pintype "bidirectional"))
      (node (ref "R12") (pin "1") (pinfunction "1_1") (pintype "passive"))
      (node (ref "R13") (pin "2") (pinfunction "2_2") (pintype "passive"))
      (node (ref "U1") (pin "42") (pinfunction "PA9_42") (pintype "bidirectional"))
    )
    (net (code "44") (name "USB_N") (class "Default")
      (node (ref "J1") (pin "9") (pinfunction "P$9_9") (pintype "bidirectional"))
      (node (ref "R9") (pin "2") (pinfunction "2_2") (pintype "passive"))
      (node (ref "U1") (pin "44") (pinfunction "PA11_44") (pintype "bidirectional"))
    )
    (net (code "45") (name "USB_P") (class "Default")
      (node (ref "J1") (pin "10") (pinfunction "P$10_10") (pintype "bidirectional"))
      (node (ref "R10") (pin "2") (pinfunction "2_2") (pintype "passive"))
      (node (ref "R11") (pin "1") (pinfunction "1_1") (pintype "passive"))
      (node (ref "U1") (pin "45") (pinfunction "PA12_45") (pintype "bidirectional"))
    )
    (net (code "46") (name "VCC") (class "Default")
      (node (ref "U3") (pin "28") (pinfunction "VCC_28") (pintype "power_in"))
    )
    (net (code "47") (name "VCORE") (class "Default")
      (node (ref "C6") (pin "1") (pinfunction "1_1") (pintype "passive"))
      (node (ref "C7") (pin "1") (pinfunction "1_1") (pintype "passive"))
      (node (ref "J3") (pin "2") (pinfunction "P$2_2") (pintype "bidirectional"))
      (node (ref "Q1") (pin "3") (pinfunction "D_3") (pintype "passive"))
      (node (ref "R7") (pin "2") (pinfunction "2_2") (pintype "passive"))
      (node (ref "TP4") (pin "1") (pinfunction "PP_1") (pintype "input"))
      (node (ref "U1") (pin "31") (pinfunction "VCAP1_31") (pintype "bidirectional"))
      (node (ref "U1") (pin "47") (pinfunction "VCAP2_47") (pintype "bidirectional"))
    )
    (net (code "48") (name "V_IN") (class "Default")
      (node (ref "C5") (pin "1") (pinfunction "1_1") (pintype "passive"))
      (node (ref "D2") (pin "A") (pinfunction "A_A") (pintype "passive"))
      (node (ref "J3") (pin "14") (pinfunction "P$14_14") (pintype "bidirectional"))
      (node (ref "TP2") (pin "1") (pinfunction "PP_1") (pintype "input"))
    )
    (net (code "49") (name "unconnected-(J1-P$1-Pad1)") (class "Default")
      (node (ref "J1") (pin "1") (pinfunction "P$1_1") (pintype "bidirectional"))
    )
    (net (code "50") (name "unconnected-(J1-P$17-Pad17)") (class "Default")
      (node (ref "J1") (pin "17") (pinfunction "P$17_17") (pintype "bidirectional"))
    )
    (net (code "51") (name "unconnected-(J2-P$15-Pad15)") (class "Default")
      (node (ref "J2") (pin "15") (pinfunction "P$15_15") (pintype "bidirectional"))
    )
    (net (code "52") (name "unconnected-(J2-P$16-Pad16)") (class "Default")
      (node (ref "J2") (pin "16") (pinfunction "P$16_16") (pintype "bidirectional"))
    )
    (net (code "53") (name "unconnected-(J2-P$17-Pad17)") (class "Default")
      (node (ref "J2") (pin "17") (pinfunction "P$17_17") (pintype "bidirectional"))
    )
    (net (code "54") (name "unconnected-(J2-P$18-Pad18)") (class "Default")
      (node (ref "J2") (pin "18") (pinfunction "P$18_18") (pintype "bidirectional"))
    )
    (net (code "55") (name "unconnected-(J2-P$19-Pad19)") (class "Default")
      (node (ref "J2") (pin "19") (pinfunction "P$19_19") (pintype "bidirectional"))
    )
    (net (code "56") (name "unconnected-(J2-P$20-Pad20)") (class "Default")
      (node (ref "J2") (pin "20") (pinfunction "P$20_20") (pintype "bidirectional"))
    )
    (net (code "57") (name "unconnected-(J3-P$12-Pad12)") (class "Default")
      (node (ref "J3") (pin "12") (pinfunction "P$12_12") (pintype "bidirectional"))
    )
    (net (code "58") (name "unconnected-(J3-P$13-Pad13)") (class "Default")
      (node (ref "J3") (pin "13") (pinfunction "P$13_13") (pintype "bidirectional"))
    )
    (net (code "59") (name "unconnected-(J3-P$15-Pad15)") (class "Default")
      (node (ref "J3") (pin "15") (pinfunction "P$15_15") (pintype "bidirectional"))
    )
    (net (code "60") (name "unconnected-(J7-ID-Pad4)") (class "Default")
      (node (ref "J7") (pin "4") (pinfunction "ID_4") (pintype "bidirectional"))
    )
    (net (code "61") (name "unconnected-(U1A-PA0-Pad14)") (class "Default")
      (node (ref "U1") (pin "14") (pinfunction "PA0_14") (pintype "bidirectional"))
    )
    (net (code "62") (name "unconnected-(U1A-PA1-Pad15)") (class "Default")
      (node (ref "U1") (pin "15") (pinfunction "PA1_15") (pintype "bidirectional"))
    )
    (net (code "63") (name "unconnected-(U1A-PA2-Pad16)") (class "Default")
      (node (ref "U1") (pin "16") (pinfunction "PA2_16") (pintype "bidirectional"))
    )
    (net (code "64") (name "unconnected-(U1A-PA3-Pad17)") (class "Default")
      (node (ref "U1") (pin "17") (pinfunction "PA3_17") (pintype "bidirectional"))
    )
    (net (code "65") (name "unconnected-(U1A-PA6-Pad22)") (class "Default")
      (node (ref "U1") (pin "22") (pinfunction "PA6_22") (pintype "bidirectional"))
    )
    (net (code "66") (name "unconnected-(U1A-PA8-Pad41)") (class "Default")
      (node (ref "U1") (pin "41") (pinfunction "PA8_41") (pintype "bidirectional"))
    )
    (net (code "67") (name "unconnected-(U1A-PB5-Pad57)") (class "Default")
      (node (ref "U1") (pin "57") (pinfunction "PB5_57") (pintype "bidirectional"))
    )
    (net (code "68") (name "unconnected-(U1A-PB6-Pad58)") (class "Default")
      (node (ref "U1") (pin "58") (pinfunction "PB6_58") (pintype "bidirectional"))
    )
    (net (code "69") (name "unconnected-(U1A-PB7-Pad59)") (class "Default")
      (node (ref "U1") (pin "59") (pinfunction "PB7_59") (pintype "bidirectional"))
    )
    (net (code "70") (name "unconnected-(U1A-PB8-Pad61)") (class "Default")
      (node (ref "U1") (pin "61") (pinfunction "PB8_61") (pintype "bidirectional"))
    )
    (net (code "71") (name "unconnected-(U1A-PB9-Pad62)") (class "Default")
      (node (ref "U1") (pin "62") (pinfunction "PB9_62") (pintype "bidirectional"))
    )
    (net (code "72") (name "unconnected-(U1A-PB10-Pad29)") (class "Default")
      (node (ref "U1") (pin "29") (pinfunction "PB10_29") (pintype "bidirectional"))
    )
    (net (code "73") (name "unconnected-(U1A-PB11-Pad30)") (class "Default")
      (node (ref "U1") (pin "30") (pinfunction "PB11_30") (pintype "bidirectional"))
    )
    (net (code "74") (name "unconnected-(U1A-PC0-Pad8)") (class "Default")
      (node (ref "U1") (pin "8") (pinfunction "PC0_8") (pintype "bidirectional"))
    )
    (net (code "75") (name "unconnected-(U1A-PC1-Pad9)") (class "Default")
      (node (ref "U1") (pin "9") (pinfunction "PC1_9") (pintype "bidirectional"))
    )
    (net (code "76") (name "unconnected-(U1A-PC3-Pad11)") (class "Default")
      (node (ref "U1") (pin "11") (pinfunction "PC3_11") (pintype "bidirectional"))
    )
    (net (code "77") (name "unconnected-(U1A-PC4-Pad24)") (class "Default")
      (node (ref "U1") (pin "24") (pinfunction "PC4_24") (pintype "bidirectional"))
    )
    (net (code "78") (name "unconnected-(U1A-PC6-Pad37)") (class "Default")
      (node (ref "U1") (pin "37") (pinfunction "PC6_37") (pintype "bidirectional"))
    )
    (net (code "79") (name "unconnected-(U1A-PC7-Pad38)") (class "Default")
      (node (ref "U1") (pin "38") (pinfunction "PC7_38") (pintype "bidirectional"))
    )
    (net (code "80") (name "unconnected-(U1A-PC8-Pad39)") (class "Default")
      (node (ref "U1") (pin "39") (pinfunction "PC8_39") (pintype "bidirectional"))
    )
    (net (code "81") (name "unconnected-(U1A-PC9-Pad40)") (class "Default")
      (node (ref "U1") (pin "40") (pinfunction "PC9_40") (pintype "bidirectional"))
    )
    (net (code "82") (name "unconnected-(U1A-PC10-Pad51)") (class "Default")
      (node (ref "U1") (pin "51") (pinfunction "PC10_51") (pintype "bidirectional"))
    )
    (net (code "83") (name "unconnected-(U1A-PC11-Pad52)") (class "Default")
      (node (ref "U1") (pin "52") (pinfunction "PC11_52") (pintype "bidirectional"))
    )
    (net (code "84") (name "unconnected-(U1A-PC12-Pad53)") (class "Default")
      (node (ref "U1") (pin "53") (pinfunction "PC12_53") (pintype "bidirectional"))
    )
    (net (code "85") (name "unconnected-(U1A-PD2-Pad54)") (class "Default")
      (node (ref "U1") (pin "54") (pinfunction "PD2_54") (pintype "bidirectional"))
    )
    (net (code "86") (name "unconnected-(U3-D2{slash}I2C_SDA-Pad20)") (class "Default")
      (node (ref "U3") (pin "20") (pinfunction "D2/I2C_SDA_20") (pintype "bidirectional"))
    )
    (net (code "87") (name "unconnected-(U3-D3-Pad21)") (class "Default")
      (node (ref "U3") (pin "21") (pinfunction "D3_21") (pintype "bidirectional"))
    )
    (net (code "88") (name "unconnected-(U3-D4-Pad22)") (class "Default")
      (node (ref "U3") (pin "22") (pinfunction "D4_22") (pintype "bidirectional"))
    )
    (net (code "89") (name "unconnected-(U3-D5-Pad23)") (class "Default")
      (node (ref "U3") (pin "23") (pinfunction "D5_23") (pintype "bidirectional"))
    )
    (net (code "90") (name "unconnected-(U3-D6-Pad24)") (class "Default")
      (node (ref "U3") (pin "24") (pinfunction "D6_24") (pintype "bidirectional"))
    )
    (net (code "91") (name "unconnected-(U3-D7-Pad25)") (class "Default")
      (node (ref "U3") (pin "25") (pinfunction "D7_25") (pintype "bidirectional"))
    )
    (net (code "92") (name "unconnected-(U3-E{slash}RD-Pad17)") (class "Default")
      (node (ref "U3") (pin "17") (pinfunction "E/RD_17") (pintype "input"))
    )
    (net (code "93") (name "unconnected-(U3-NC-Pad7)") (class "Default")
      (node (ref "U3") (pin "7") (pinfunction "NC_7") (pintype "no_connect"))
    )
    (net (code "94") (name "unconnected-(U3-R{slash}W-Pad16)") (class "Default")
      (node (ref "U3") (pin "16") (pinfunction "R/W_16") (pintype "input"))
    )
    (net (code "95") (name "~{RESET}") (class "Default")
      (node (ref "C2") (pin "1") (pinfunction "1_1") (pintype "passive"))
      (node (ref "J1") (pin "11") (pinfunction "P$11_11") (pintype "bidirectional"))
      (node (ref "J2") (pin "8") (pinfunction "P$8_8") (pintype "bidirectional"))
      (node (ref "J4") (pin "10") (pinfunction "P$10_10") (pintype "bidirectional"))
      (node (ref "U1") (pin "7") (pinfunction "~{RST}_7") (pintype "bidirectional"))
    )
  )
)
